# stm32F7_144.net
KiCad netlist of a schematic drawn in Altium Designer
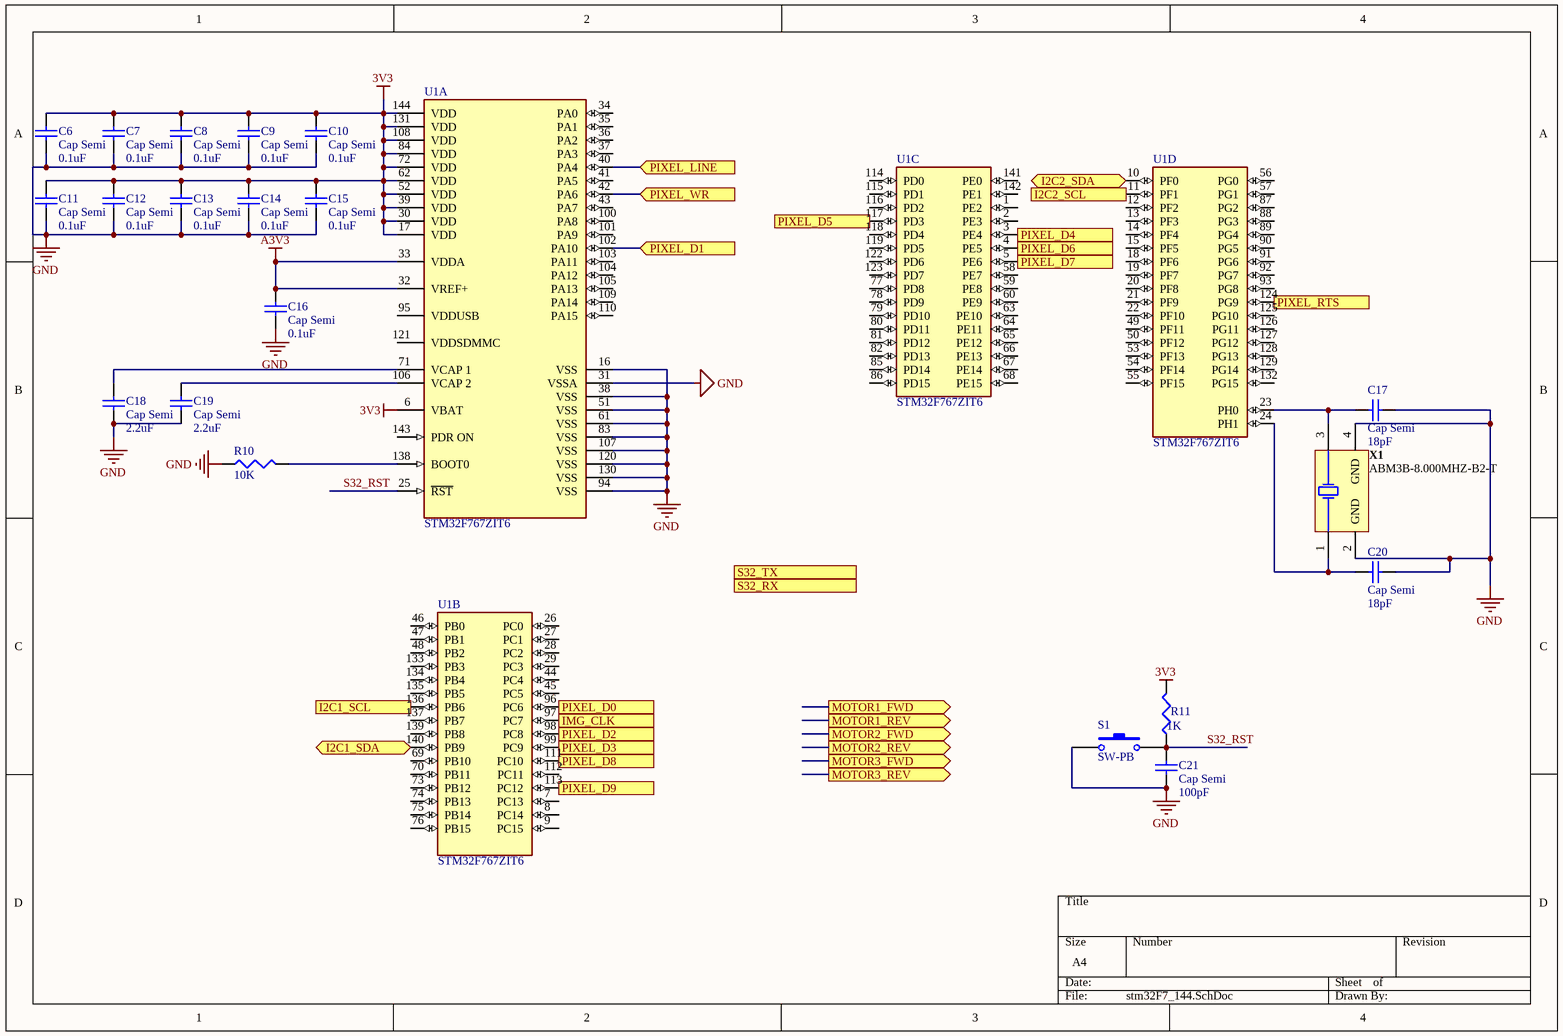
[diagram p0: stm32F7_144.SchDoc]

(export (version "E")
  (design (tool "Eeschema 10.0.6"))
  (components
    (comp (ref "C6")
      (value "Cap Semi")
      (footprint "C1206")
      (description "Capacitor (Semiconductor SIM Model)")
      (fields (field (name "ALTIUM_VALUE") "0.1uF") (field (name "PUBLISHER") "Altium Limited"))
      (libsource (lib "Miscellaneous Devices") (part "Cap Semi"))
    )
    (comp (ref "C7")
      (value "Cap Semi")
      (footprint "C1206")
      (description "Capacitor (Semiconductor SIM Model)")
      (fields (field (name "ALTIUM_VALUE") "0.1uF") (field (name "PUBLISHER") "Altium Limited"))
      (libsource (lib "Miscellaneous Devices") (part "Cap Semi"))
    )
    (comp (ref "C8")
      (value "Cap Semi")
      (footprint "C1206")
      (description "Capacitor (Semiconductor SIM Model)")
      (fields (field (name "ALTIUM_VALUE") "0.1uF") (field (name "PUBLISHER") "Altium Limited"))
      (libsource (lib "Miscellaneous Devices") (part "Cap Semi"))
    )
    (comp (ref "C9")
      (value "Cap Semi")
      (footprint "C1206")
      (description "Capacitor (Semiconductor SIM Model)")
      (fields (field (name "ALTIUM_VALUE") "0.1uF") (field (name "PUBLISHER") "Altium Limited"))
      (libsource (lib "Miscellaneous Devices") (part "Cap Semi"))
    )
    (comp (ref "C10")
      (value "Cap Semi")
      (footprint "C1206")
      (description "Capacitor (Semiconductor SIM Model)")
      (fields (field (name "ALTIUM_VALUE") "0.1uF") (field (name "PUBLISHER") "Altium Limited"))
      (libsource (lib "Miscellaneous Devices") (part "Cap Semi"))
    )
    (comp (ref "C11")
      (value "Cap Semi")
      (footprint "C1206")
      (description "Capacitor (Semiconductor SIM Model)")
      (fields (field (name "ALTIUM_VALUE") "0.1uF") (field (name "PUBLISHER") "Altium Limited"))
      (libsource (lib "Miscellaneous Devices") (part "Cap Semi"))
    )
    (comp (ref "C12")
      (value "Cap Semi")
      (footprint "C1206")
      (description "Capacitor (Semiconductor SIM Model)")
      (fields (field (name "ALTIUM_VALUE") "0.1uF") (field (name "PUBLISHER") "Altium Limited"))
      (libsource (lib "Miscellaneous Devices") (part "Cap Semi"))
    )
    (comp (ref "C13")
      (value "Cap Semi")
      (footprint "C1206")
      (description "Capacitor (Semiconductor SIM Model)")
      (fields (field (name "ALTIUM_VALUE") "0.1uF") (field (name "PUBLISHER") "Altium Limited"))
      (libsource (lib "Miscellaneous Devices") (part "Cap Semi"))
    )
    (comp (ref "C14")
      (value "Cap Semi")
      (footprint "C1206")
      (description "Capacitor (Semiconductor SIM Model)")
      (fields (field (name "ALTIUM_VALUE") "0.1uF") (field (name "PUBLISHER") "Altium Limited"))
      (libsource (lib "Miscellaneous Devices") (part "Cap Semi"))
    )
    (comp (ref "C15")
      (value "Cap Semi")
      (footprint "C1206")
      (description "Capacitor (Semiconductor SIM Model)")
      (fields (field (name "ALTIUM_VALUE") "0.1uF") (field (name "PUBLISHER") "Altium Limited"))
      (libsource (lib "Miscellaneous Devices") (part "Cap Semi"))
    )
    (comp (ref "C16")
      (value "Cap Semi")
      (footprint "C1206")
      (description "Capacitor (Semiconductor SIM Model)")
      (fields (field (name "ALTIUM_VALUE") "0.1uF") (field (name "PUBLISHER") "Altium Limited"))
      (libsource (lib "Miscellaneous Devices") (part "Cap Semi"))
    )
    (comp (ref "C17")
      (value "Cap Semi")
      (footprint "C1206")
      (description "Capacitor (Semiconductor SIM Model)")
      (fields (field (name "ALTIUM_VALUE") "18pF") (field (name "PUBLISHER") "Altium Limited"))
      (libsource (lib "Miscellaneous Devices") (part "Cap Semi"))
    )
    (comp (ref "C18")
      (value "Cap Semi")
      (footprint "C1206")
      (description "Capacitor (Semiconductor SIM Model)")
      (fields (field (name "ALTIUM_VALUE") "2.2uF") (field (name "PUBLISHER") "Altium Limited"))
      (libsource (lib "Miscellaneous Devices") (part "Cap Semi"))
    )
    (comp (ref "C19")
      (value "Cap Semi")
      (footprint "C1206")
      (description "Capacitor (Semiconductor SIM Model)")
      (fields (field (name "ALTIUM_VALUE") "2.2uF") (field (name "PUBLISHER") "Altium Limited"))
      (libsource (lib "Miscellaneous Devices") (part "Cap Semi"))
    )
    (comp (ref "C20")
      (value "Cap Semi")
      (footprint "C1206")
      (description "Capacitor (Semiconductor SIM Model)")
      (fields (field (name "ALTIUM_VALUE") "18pF") (field (name "PUBLISHER") "Altium Limited"))
      (libsource (lib "Miscellaneous Devices") (part "Cap Semi"))
    )
    (comp (ref "C21")
      (value "Cap Semi")
      (footprint "C1206")
      (description "Capacitor (Semiconductor SIM Model)")
      (fields (field (name "ALTIUM_VALUE") "100pF") (field (name "PUBLISHER") "Altium Limited"))
      (libsource (lib "Miscellaneous Devices") (part "Cap Semi"))
    )
    (comp (ref "R10")
      (value "10K")
      (footprint "J1-0603")
      (description "Resistor")
      (fields (field (name "Comment") "Res3") (field (name "PUBLISHER") "Altium Limited"))
      (libsource (lib "Miscellaneous Devices") (part "Res3"))
    )
    (comp (ref "R11")
      (value "1K")
      (footprint "J1-0603")
      (description "Resistor")
      (fields (field (name "Comment") "Res3") (field (name "PUBLISHER") "Altium Limited"))
      (libsource (lib "Miscellaneous Devices") (part "Res3"))
    )
    (comp (ref "S1")
      (value "SW-PB")
      (footprint "SPST-2")
      (description "Switch")
      (fields (field (name "PUBLISHER") "Altium Limited"))
      (libsource (lib "Miscellaneous Devices") (part "SW-PB"))
    )
    (comp (ref "U1")
      (value "STM32F767ZIT6")
      (footprint "FP-LQFP144-1A-MFG")
      (description "IC MCU 32BIT 2MB FLASH 144LQFP")
      (fields
        (field (name "OCTOPART") "https://octopart.com/stm32f767zit6-stmicroelectronics-70527068")
        (field (name "MANUFACTURER") "STMicroelectronics")
      )
      (libsource (lib "Altium Content Vault") (part "5045e889cff10565096e715f5715cbd"))
    )
    (comp (ref "X1")
      (value "ABM3B-8.000MHZ-B2-T")
      (footprint "ABRA-ABM3B_V")
      (description "Ceramic SMD Crystal, 8 MHz, +/- 20 ppm, 200 Ohm, -20 to 70 degC, 4-Pin SMD, RoHS, Tape and Reel")
      (libsource (lib "Altium Content Vault") (part "XTAL-1-3-4"))
    )
  )
  (nets
    (net (code "1") (name "/I2C1_SCL") (class "Default")
      (node (ref "U1") (pin "136") (pinfunction "PB6_136") (pintype "bidirectional"))
    )
    (net (code "2") (name "/I2C1_SDA") (class "Default")
      (node (ref "U1") (pin "140") (pinfunction "PB9_140") (pintype "bidirectional"))
    )
    (net (code "3") (name "/I2C2_SCL") (class "Default")
      (node (ref "U1") (pin "11") (pinfunction "PF1_11") (pintype "bidirectional"))
    )
    (net (code "4") (name "/I2C2_SDA") (class "Default")
      (node (ref "U1") (pin "10") (pinfunction "PF0_10") (pintype "bidirectional"))
    )
    (net (code "5") (name "/IMG_CLK") (class "Default")
      (node (ref "U1") (pin "97") (pinfunction "PC7_97") (pintype "bidirectional"))
    )
    (net (code "12") (name "/PIXEL_D0") (class "Default")
      (node (ref "U1") (pin "96") (pinfunction "PC6_96") (pintype "bidirectional"))
    )
    (net (code "13") (name "/PIXEL_D1") (class "Default")
      (node (ref "U1") (pin "102") (pinfunction "PA10_102") (pintype "bidirectional"))
    )
    (net (code "14") (name "/PIXEL_D2") (class "Default")
      (node (ref "U1") (pin "98") (pinfunction "PC8_98") (pintype "bidirectional"))
    )
    (net (code "15") (name "/PIXEL_D3") (class "Default")
      (node (ref "U1") (pin "99") (pinfunction "PC9_99") (pintype "bidirectional"))
    )
    (net (code "16") (name "/PIXEL_D4") (class "Default")
      (node (ref "U1") (pin "3") (pinfunction "PE4_3") (pintype "bidirectional"))
    )
    (net (code "17") (name "/PIXEL_D5") (class "Default")
      (node (ref "U1") (pin "117") (pinfunction "PD3_117") (pintype "bidirectional"))
    )
    (net (code "18") (name "/PIXEL_D6") (class "Default")
      (node (ref "U1") (pin "4") (pinfunction "PE5_4") (pintype "bidirectional"))
    )
    (net (code "19") (name "/PIXEL_D7") (class "Default")
      (node (ref "U1") (pin "5") (pinfunction "PE6_5") (pintype "bidirectional"))
    )
    (net (code "20") (name "/PIXEL_D8") (class "Default")
      (node (ref "U1") (pin "111") (pinfunction "PC10_111") (pintype "bidirectional"))
    )
    (net (code "21") (name "/PIXEL_D9") (class "Default")
      (node (ref "U1") (pin "113") (pinfunction "PC12_113") (pintype "bidirectional"))
    )
    (net (code "22") (name "/PIXEL_LINE") (class "Default")
      (node (ref "U1") (pin "40") (pinfunction "PA4_40") (pintype "bidirectional"))
    )
    (net (code "23") (name "/PIXEL_RTS") (class "Default")
      (node (ref "U1") (pin "124") (pinfunction "PG9_124") (pintype "bidirectional"))
    )
    (net (code "24") (name "/PIXEL_WR") (class "Default")
      (node (ref "U1") (pin "42") (pinfunction "PA6_42") (pintype "bidirectional"))
    )
    (net (code "25") (name "/S32_RST") (class "Default")
      (node (ref "C21") (pin "2") (pinfunction "2_2") (pintype "passive"))
      (node (ref "R11") (pin "1") (pinfunction "1_1") (pintype "passive"))
      (node (ref "S1") (pin "2") (pinfunction "2_2") (pintype "passive"))
      (node (ref "U1") (pin "25") (pinfunction "~{RST}_25") (pintype "input"))
    )
    (net (code "28") (name "3V3") (class "Default")
      (node (ref "C10") (pin "2") (pinfunction "2_2") (pintype "passive"))
      (node (ref "C11") (pin "2") (pinfunction "2_2") (pintype "passive"))
      (node (ref "C12") (pin "2") (pinfunction "2_2") (pintype "passive"))
      (node (ref "C13") (pin "2") (pinfunction "2_2") (pintype "passive"))
      (node (ref "C14") (pin "2") (pinfunction "2_2") (pintype "passive"))
      (node (ref "C15") (pin "2") (pinfunction "2_2") (pintype "passive"))
      (node (ref "C6") (pin "2") (pinfunction "2_2") (pintype "passive"))
      (node (ref "C7") (pin "2") (pinfunction "2_2") (pintype "passive"))
      (node (ref "C8") (pin "2") (pinfunction "2_2") (pintype "passive"))
      (node (ref "C9") (pin "2") (pinfunction "2_2") (pintype "passive"))
      (node (ref "U1") (pin "108") (pinfunction "VDD_108") (pintype "power_in"))
      (node (ref "U1") (pin "131") (pinfunction "VDD_131") (pintype "power_in"))
      (node (ref "U1") (pin "144") (pinfunction "VDD_144") (pintype "power_in"))
      (node (ref "U1") (pin "17") (pinfunction "VDD_17") (pintype "power_in"))
      (node (ref "U1") (pin "30") (pinfunction "VDD_30") (pintype "power_in"))
      (node (ref "U1") (pin "39") (pinfunction "VDD_39") (pintype "power_in"))
      (node (ref "U1") (pin "52") (pinfunction "VDD_52") (pintype "power_in"))
      (node (ref "U1") (pin "6") (pinfunction "VBAT_6") (pintype "power_in"))
      (node (ref "U1") (pin "62") (pinfunction "VDD_62") (pintype "power_in"))
      (node (ref "U1") (pin "72") (pinfunction "VDD_72") (pintype "power_in"))
      (node (ref "U1") (pin "84") (pinfunction "VDD_84") (pintype "power_in"))
    )
    (net (code "29") (name "A3V3") (class "Default")
      (node (ref "C16") (pin "2") (pinfunction "2_2") (pintype "passive"))
      (node (ref "U1") (pin "32") (pinfunction "VREF+_32") (pintype "power_in"))
      (node (ref "U1") (pin "33") (pinfunction "VDDA_33") (pintype "power_in"))
    )
    (net (code "30") (name "GND") (class "Default")
      (node (ref "C10") (pin "1") (pinfunction "1_1") (pintype "passive"))
      (node (ref "C11") (pin "1") (pinfunction "1_1") (pintype "passive"))
      (node (ref "C12") (pin "1") (pinfunction "1_1") (pintype "passive"))
      (node (ref "C13") (pin "1") (pinfunction "1_1") (pintype "passive"))
      (node (ref "C14") (pin "1") (pinfunction "1_1") (pintype "passive"))
      (node (ref "C15") (pin "1") (pinfunction "1_1") (pintype "passive"))
      (node (ref "C16") (pin "1") (pinfunction "1_1") (pintype "passive"))
      (node (ref "C17") (pin "2") (pinfunction "2_2") (pintype "passive"))
      (node (ref "C18") (pin "1") (pinfunction "1_1") (pintype "passive"))
      (node (ref "C19") (pin "1") (pinfunction "1_1") (pintype "passive"))
      (node (ref "C20") (pin "2") (pinfunction "2_2") (pintype "passive"))
      (node (ref "C21") (pin "1") (pinfunction "1_1") (pintype "passive"))
      (node (ref "C6") (pin "1") (pinfunction "1_1") (pintype "passive"))
      (node (ref "C7") (pin "1") (pinfunction "1_1") (pintype "passive"))
      (node (ref "C8") (pin "1") (pinfunction "1_1") (pintype "passive"))
      (node (ref "C9") (pin "1") (pinfunction "1_1") (pintype "passive"))
      (node (ref "R10") (pin "1") (pinfunction "1_1") (pintype "passive"))
      (node (ref "S1") (pin "1") (pinfunction "1_1") (pintype "passive"))
      (node (ref "U1") (pin "107") (pinfunction "VSS_107") (pintype "power_in"))
      (node (ref "U1") (pin "120") (pinfunction "VSS_120") (pintype "power_in"))
      (node (ref "U1") (pin "130") (pinfunction "VSS_130") (pintype "power_in"))
      (node (ref "U1") (pin "16") (pinfunction "VSS_16") (pintype "power_in"))
      (node (ref "U1") (pin "31") (pinfunction "VSSA_31") (pintype "power_in"))
      (node (ref "U1") (pin "38") (pinfunction "VSS_38") (pintype "power_in"))
      (node (ref "U1") (pin "51") (pinfunction "VSS_51") (pintype "power_in"))
      (node (ref "U1") (pin "61") (pinfunction "VSS_61") (pintype "power_in"))
      (node (ref "U1") (pin "83") (pinfunction "VSS_83") (pintype "power_in"))
      (node (ref "U1") (pin "94") (pinfunction "VSS_94") (pintype "power_in"))
      (node (ref "X1") (pin "2") (pinfunction "GND_2") (pintype "power_in"))
      (node (ref "X1") (pin "4") (pinfunction "GND_4") (pintype "power_in"))
    )
    (net (code "31") (name "Net-(U1A-BOOT0)") (class "Default")
      (node (ref "R10") (pin "2") (pinfunction "2_2") (pintype "passive"))
      (node (ref "U1") (pin "138") (pinfunction "BOOT0_138") (pintype "input"))
    )
    (net (code "32") (name "Net-(U1A-VCAP_1)") (class "Default")
      (node (ref "C18") (pin "2") (pinfunction "2_2") (pintype "passive"))
      (node (ref "U1") (pin "71") (pinfunction "VCAP_1_71") (pintype "power_in"))
    )
    (net (code "33") (name "Net-(U1A-VCAP_2)") (class "Default")
      (node (ref "C19") (pin "2") (pinfunction "2_2") (pintype "passive"))
      (node (ref "U1") (pin "106") (pinfunction "VCAP_2_106") (pintype "power_in"))
    )
    (net (code "34") (name "Net-(U1D-PH0)") (class "Default")
      (node (ref "C17") (pin "1") (pinfunction "1_1") (pintype "passive"))
      (node (ref "U1") (pin "23") (pinfunction "PH0_23") (pintype "bidirectional"))
      (node (ref "X1") (pin "3") (pinfunction "X2_3") (pintype "passive"))
    )
    (net (code "35") (name "Net-(U1D-PH1)") (class "Default")
      (node (ref "C20") (pin "1") (pinfunction "1_1") (pintype "passive"))
      (node (ref "U1") (pin "24") (pinfunction "PH1_24") (pintype "bidirectional"))
      (node (ref "X1") (pin "1") (pinfunction "X1_1") (pintype "passive"))
    )
    (net (code "36") (name "unconnected-(R11-Pad2)") (class "Default")
      (node (ref "R11") (pin "2") (pinfunction "2_2") (pintype "passive"))
    )
    (net (code "37") (name "unconnected-(U1A-PA0-Pad34)") (class "Default")
      (node (ref "U1") (pin "34") (pinfunction "PA0_34") (pintype "bidirectional"))
    )
    (net (code "38") (name "unconnected-(U1A-PA1-Pad35)") (class "Default")
      (node (ref "U1") (pin "35") (pinfunction "PA1_35") (pintype "bidirectional"))
    )
    (net (code "39") (name "unconnected-(U1A-PA2-Pad36)") (class "Default")
      (node (ref "U1") (pin "36") (pinfunction "PA2_36") (pintype "bidirectional"))
    )
    (net (code "40") (name "unconnected-(U1A-PA3-Pad37)") (class "Default")
      (node (ref "U1") (pin "37") (pinfunction "PA3_37") (pintype "bidirectional"))
    )
    (net (code "41") (name "unconnected-(U1A-PA5-Pad41)") (class "Default")
      (node (ref "U1") (pin "41") (pinfunction "PA5_41") (pintype "bidirectional"))
    )
    (net (code "42") (name "unconnected-(U1A-PA7-Pad43)") (class "Default")
      (node (ref "U1") (pin "43") (pinfunction "PA7_43") (pintype "bidirectional"))
    )
    (net (code "43") (name "unconnected-(U1A-PA8-Pad100)") (class "Default")
      (node (ref "U1") (pin "100") (pinfunction "PA8_100") (pintype "bidirectional"))
    )
    (net (code "44") (name "unconnected-(U1A-PA9-Pad101)") (class "Default")
      (node (ref "U1") (pin "101") (pinfunction "PA9_101") (pintype "bidirectional"))
    )
    (net (code "45") (name "unconnected-(U1A-PA11-Pad103)") (class "Default")
      (node (ref "U1") (pin "103") (pinfunction "PA11_103") (pintype "bidirectional"))
    )
    (net (code "46") (name "unconnected-(U1A-PA12-Pad104)") (class "Default")
      (node (ref "U1") (pin "104") (pinfunction "PA12_104") (pintype "bidirectional"))
    )
    (net (code "47") (name "unconnected-(U1A-PA13-Pad105)") (class "Default")
      (node (ref "U1") (pin "105") (pinfunction "PA13_105") (pintype "bidirectional"))
    )
    (net (code "48") (name "unconnected-(U1A-PA14-Pad109)") (class "Default")
      (node (ref "U1") (pin "109") (pinfunction "PA14_109") (pintype "bidirectional"))
    )
    (net (code "49") (name "unconnected-(U1A-PA15-Pad110)") (class "Default")
      (node (ref "U1") (pin "110") (pinfunction "PA15_110") (pintype "bidirectional"))
    )
    (net (code "50") (name "unconnected-(U1A-PDR_ON-Pad143)") (class "Default")
      (node (ref "U1") (pin "143") (pinfunction "PDR_ON_143") (pintype "input"))
    )
    (net (code "51") (name "unconnected-(U1A-VDDSDMMC-Pad121)") (class "Default")
      (node (ref "U1") (pin "121") (pinfunction "VDDSDMMC_121") (pintype "power_in"))
    )
    (net (code "52") (name "unconnected-(U1A-VDDUSB-Pad95)") (class "Default")
      (node (ref "U1") (pin "95") (pinfunction "VDDUSB_95") (pintype "power_in"))
    )
    (net (code "53") (name "unconnected-(U1B-PB0-Pad46)") (class "Default")
      (node (ref "U1") (pin "46") (pinfunction "PB0_46") (pintype "bidirectional"))
    )
    (net (code "54") (name "unconnected-(U1B-PB1-Pad47)") (class "Default")
      (node (ref "U1") (pin "47") (pinfunction "PB1_47") (pintype "bidirectional"))
    )
    (net (code "55") (name "unconnected-(U1B-PB2-Pad48)") (class "Default")
      (node (ref "U1") (pin "48") (pinfunction "PB2_48") (pintype "bidirectional"))
    )
    (net (code "56") (name "unconnected-(U1B-PB3-Pad133)") (class "Default")
      (node (ref "U1") (pin "133") (pinfunction "PB3_133") (pintype "bidirectional"))
    )
    (net (code "57") (name "unconnected-(U1B-PB4-Pad134)") (class "Default")
      (node (ref "U1") (pin "134") (pinfunction "PB4_134") (pintype "bidirectional"))
    )
    (net (code "58") (name "unconnected-(U1B-PB5-Pad135)") (class "Default")
      (node (ref "U1") (pin "135") (pinfunction "PB5_135") (pintype "bidirectional"))
    )
    (net (code "59") (name "unconnected-(U1B-PB7-Pad137)") (class "Default")
      (node (ref "U1") (pin "137") (pinfunction "PB7_137") (pintype "bidirectional"))
    )
    (net (code "60") (name "unconnected-(U1B-PB8-Pad139)") (class "Default")
      (node (ref "U1") (pin "139") (pinfunction "PB8_139") (pintype "bidirectional"))
    )
    (net (code "61") (name "unconnected-(U1B-PB10-Pad69)") (class "Default")
      (node (ref "U1") (pin "69") (pinfunction "PB10_69") (pintype "bidirectional"))
    )
    (net (code "62") (name "unconnected-(U1B-PB11-Pad70)") (class "Default")
      (node (ref "U1") (pin "70") (pinfunction "PB11_70") (pintype "bidirectional"))
    )
    (net (code "63") (name "unconnected-(U1B-PB12-Pad73)") (class "Default")
      (node (ref "U1") (pin "73") (pinfunction "PB12_73") (pintype "bidirectional"))
    )
    (net (code "64") (name "unconnected-(U1B-PB13-Pad74)") (class "Default")
      (node (ref "U1") (pin "74") (pinfunction "PB13_74") (pintype "bidirectional"))
    )
    (net (code "65") (name "unconnected-(U1B-PB14-Pad75)") (class "Default")
      (node (ref "U1") (pin "75") (pinfunction "PB14_75") (pintype "bidirectional"))
    )
    (net (code "66") (name "unconnected-(U1B-PB15-Pad76)") (class "Default")
      (node (ref "U1") (pin "76") (pinfunction "PB15_76") (pintype "bidirectional"))
    )
    (net (code "67") (name "unconnected-(U1B-PC0-Pad26)") (class "Default")
      (node (ref "U1") (pin "26") (pinfunction "PC0_26") (pintype "bidirectional"))
    )
    (net (code "68") (name "unconnected-(U1B-PC1-Pad27)") (class "Default")
      (node (ref "U1") (pin "27") (pinfunction "PC1_27") (pintype "bidirectional"))
    )
    (net (code "69") (name "unconnected-(U1B-PC2-Pad28)") (class "Default")
      (node (ref "U1") (pin "28") (pinfunction "PC2_28") (pintype "bidirectional"))
    )
    (net (code "70") (name "unconnected-(U1B-PC3-Pad29)") (class "Default")
      (node (ref "U1") (pin "29") (pinfunction "PC3_29") (pintype "bidirectional"))
    )
    (net (code "71") (name "unconnected-(U1B-PC4-Pad44)") (class "Default")
      (node (ref "U1") (pin "44") (pinfunction "PC4_44") (pintype "bidirectional"))
    )
    (net (code "72") (name "unconnected-(U1B-PC5-Pad45)") (class "Default")
      (node (ref "U1") (pin "45") (pinfunction "PC5_45") (pintype "bidirectional"))
    )
    (net (code "73") (name "unconnected-(U1B-PC11-Pad112)") (class "Default")
      (node (ref "U1") (pin "112") (pinfunction "PC11_112") (pintype "bidirectional"))
    )
    (net (code "74") (name "unconnected-(U1B-PC13-Pad7)") (class "Default")
      (node (ref "U1") (pin "7") (pinfunction "PC13_7") (pintype "bidirectional"))
    )
    (net (code "75") (name "unconnected-(U1B-PC14-Pad8)") (class "Default")
      (node (ref "U1") (pin "8") (pinfunction "PC14_8") (pintype "bidirectional"))
    )
    (net (code "76") (name "unconnected-(U1B-PC15-Pad9)") (class "Default")
      (node (ref "U1") (pin "9") (pinfunction "PC15_9") (pintype "bidirectional"))
    )
    (net (code "77") (name "unconnected-(U1C-PD0-Pad114)") (class "Default")
      (node (ref "U1") (pin "114") (pinfunction "PD0_114") (pintype "bidirectional"))
    )
    (net (code "78") (name "unconnected-(U1C-PD1-Pad115)") (class "Default")
      (node (ref "U1") (pin "115") (pinfunction "PD1_115") (pintype "bidirectional"))
    )
    (net (code "79") (name "unconnected-(U1C-PD2-Pad116)") (class "Default")
      (node (ref "U1") (pin "116") (pinfunction "PD2_116") (pintype "bidirectional"))
    )
    (net (code "80") (name "unconnected-(U1C-PD4-Pad118)") (class "Default")
      (node (ref "U1") (pin "118") (pinfunction "PD4_118") (pintype "bidirectional"))
    )
    (net (code "81") (name "unconnected-(U1C-PD5-Pad119)") (class "Default")
      (node (ref "U1") (pin "119") (pinfunction "PD5_119") (pintype "bidirectional"))
    )
    (net (code "82") (name "unconnected-(U1C-PD6-Pad122)") (class "Default")
      (node (ref "U1") (pin "122") (pinfunction "PD6_122") (pintype "bidirectional"))
    )
    (net (code "83") (name "unconnected-(U1C-PD7-Pad123)") (class "Default")
      (node (ref "U1") (pin "123") (pinfunction "PD7_123") (pintype "bidirectional"))
    )
    (net (code "84") (name "unconnected-(U1C-PD8-Pad77)") (class "Default")
      (node (ref "U1") (pin "77") (pinfunction "PD8_77") (pintype "bidirectional"))
    )
    (net (code "85") (name "unconnected-(U1C-PD9-Pad78)") (class "Default")
      (node (ref "U1") (pin "78") (pinfunction "PD9_78") (pintype "bidirectional"))
    )
    (net (code "86") (name "unconnected-(U1C-PD10-Pad79)") (class "Default")
      (node (ref "U1") (pin "79") (pinfunction "PD10_79") (pintype "bidirectional"))
    )
    (net (code "87") (name "unconnected-(U1C-PD11-Pad80)") (class "Default")
      (node (ref "U1") (pin "80") (pinfunction "PD11_80") (pintype "bidirectional"))
    )
    (net (code "88") (name "unconnected-(U1C-PD12-Pad81)") (class "Default")
      (node (ref "U1") (pin "81") (pinfunction "PD12_81") (pintype "bidirectional"))
    )
    (net (code "89") (name "unconnected-(U1C-PD13-Pad82)") (class "Default")
      (node (ref "U1") (pin "82") (pinfunction "PD13_82") (pintype "bidirectional"))
    )
    (net (code "90") (name "unconnected-(U1C-PD14-Pad85)") (class "Default")
      (node (ref "U1") (pin "85") (pinfunction "PD14_85") (pintype "bidirectional"))
    )
    (net (code "91") (name "unconnected-(U1C-PD15-Pad86)") (class "Default")
      (node (ref "U1") (pin "86") (pinfunction "PD15_86") (pintype "bidirectional"))
    )
    (net (code "92") (name "unconnected-(U1C-PE0-Pad141)") (class "Default")
      (node (ref "U1") (pin "141") (pinfunction "PE0_141") (pintype "bidirectional"))
    )
    (net (code "93") (name "unconnected-(U1C-PE1-Pad142)") (class "Default")
      (node (ref "U1") (pin "142") (pinfunction "PE1_142") (pintype "bidirectional"))
    )
    (net (code "94") (name "unconnected-(U1C-PE2-Pad1)") (class "Default")
      (node (ref "U1") (pin "1") (pinfunction "PE2_1") (pintype "bidirectional"))
    )
    (net (code "95") (name "unconnected-(U1C-PE3-Pad2)") (class "Default")
      (node (ref "U1") (pin "2") (pinfunction "PE3_2") (pintype "bidirectional"))
    )
    (net (code "96") (name "unconnected-(U1C-PE7-Pad58)") (class "Default")
      (node (ref "U1") (pin "58") (pinfunction "PE7_58") (pintype "bidirectional"))
    )
    (net (code "97") (name "unconnected-(U1C-PE8-Pad59)") (class "Default")
      (node (ref "U1") (pin "59") (pinfunction "PE8_59") (pintype "bidirectional"))
    )
    (net (code "98") (name "unconnected-(U1C-PE9-Pad60)") (class "Default")
      (node (ref "U1") (pin "60") (pinfunction "PE9_60") (pintype "bidirectional"))
    )
    (net (code "99") (name "unconnected-(U1C-PE10-Pad63)") (class "Default")
      (node (ref "U1") (pin "63") (pinfunction "PE10_63") (pintype "bidirectional"))
    )
    (net (code "100") (name "unconnected-(U1C-PE11-Pad64)") (class "Default")
      (node (ref "U1") (pin "64") (pinfunction "PE11_64") (pintype "bidirectional"))
    )
    (net (code "101") (name "unconnected-(U1C-PE12-Pad65)") (class "Default")
      (node (ref "U1") (pin "65") (pinfunction "PE12_65") (pintype "bidirectional"))
    )
    (net (code "102") (name "unconnected-(U1C-PE13-Pad66)") (class "Default")
      (node (ref "U1") (pin "66") (pinfunction "PE13_66") (pintype "bidirectional"))
    )
    (net (code "103") (name "unconnected-(U1C-PE14-Pad67)") (class "Default")
      (node (ref "U1") (pin "67") (pinfunction "PE14_67") (pintype "bidirectional"))
    )
    (net (code "104") (name "unconnected-(U1C-PE15-Pad68)") (class "Default")
      (node (ref "U1") (pin "68") (pinfunction "PE15_68") (pintype "bidirectional"))
    )
    (net (code "105") (name "unconnected-(U1D-PF2-Pad12)") (class "Default")
      (node (ref "U1") (pin "12") (pinfunction "PF2_12") (pintype "bidirectional"))
    )
    (net (code "106") (name "unconnected-(U1D-PF3-Pad13)") (class "Default")
      (node (ref "U1") (pin "13") (pinfunction "PF3_13") (pintype "bidirectional"))
    )
    (net (code "107") (name "unconnected-(U1D-PF4-Pad14)") (class "Default")
      (node (ref "U1") (pin "14") (pinfunction "PF4_14") (pintype "bidirectional"))
    )
    (net (code "108") (name "unconnected-(U1D-PF5-Pad15)") (class "Default")
      (node (ref "U1") (pin "15") (pinfunction "PF5_15") (pintype "bidirectional"))
    )
    (net (code "109") (name "unconnected-(U1D-PF6-Pad18)") (class "Default")
      (node (ref "U1") (pin "18") (pinfunction "PF6_18") (pintype "bidirectional"))
    )
    (net (code "110") (name "unconnected-(U1D-PF7-Pad19)") (class "Default")
      (node (ref "U1") (pin "19") (pinfunction "PF7_19") (pintype "bidirectional"))
    )
    (net (code "111") (name "unconnected-(U1D-PF8-Pad20)") (class "Default")
      (node (ref "U1") (pin "20") (pinfunction "PF8_20") (pintype "bidirectional"))
    )
    (net (code "112") (name "unconnected-(U1D-PF9-Pad21)") (class "Default")
      (node (ref "U1") (pin "21") (pinfunction "PF9_21") (pintype "bidirectional"))
    )
    (net (code "113") (name "unconnected-(U1D-PF10-Pad22)") (class "Default")
      (node (ref "U1") (pin "22") (pinfunction "PF10_22") (pintype "bidirectional"))
    )
    (net (code "114") (name "unconnected-(U1D-PF11-Pad49)") (class "Default")
      (node (ref "U1") (pin "49") (pinfunction "PF11_49") (pintype "bidirectional"))
    )
    (net (code "115") (name "unconnected-(U1D-PF12-Pad50)") (class "Default")
      (node (ref "U1") (pin "50") (pinfunction "PF12_50") (pintype "bidirectional"))
    )
    (net (code "116") (name "unconnected-(U1D-PF13-Pad53)") (class "Default")
      (node (ref "U1") (pin "53") (pinfunction "PF13_53") (pintype "bidirectional"))
    )
    (net (code "117") (name "unconnected-(U1D-PF14-Pad54)") (class "Default")
      (node (ref "U1") (pin "54") (pinfunction "PF14_54") (pintype "bidirectional"))
    )
    (net (code "118") (name "unconnected-(U1D-PF15-Pad55)") (class "Default")
      (node (ref "U1") (pin "55") (pinfunction "PF15_55") (pintype "bidirectional"))
    )
    (net (code "119") (name "unconnected-(U1D-PG0-Pad56)") (class "Default")
      (node (ref "U1") (pin "56") (pinfunction "PG0_56") (pintype "bidirectional"))
    )
    (net (code "120") (name "unconnected-(U1D-PG1-Pad57)") (class "Default")
      (node (ref "U1") (pin "57") (pinfunction "PG1_57") (pintype "bidirectional"))
    )
    (net (code "121") (name "unconnected-(U1D-PG2-Pad87)") (class "Default")
      (node (ref "U1") (pin "87") (pinfunction "PG2_87") (pintype "bidirectional"))
    )
    (net (code "122") (name "unconnected-(U1D-PG3-Pad88)") (class "Default")
      (node (ref "U1") (pin "88") (pinfunction "PG3_88") (pintype "bidirectional"))
    )
    (net (code "123") (name "unconnected-(U1D-PG4-Pad89)") (class "Default")
      (node (ref "U1") (pin "89") (pinfunction "PG4_89") (pintype "bidirectional"))
    )
    (net (code "124") (name "unconnected-(U1D-PG5-Pad90)") (class "Default")
      (node (ref "U1") (pin "90") (pinfunction "PG5_90") (pintype "bidirectional"))
    )
    (net (code "125") (name "unconnected-(U1D-PG6-Pad91)") (class "Default")
      (node (ref "U1") (pin "91") (pinfunction "PG6_91") (pintype "bidirectional"))
    )
    (net (code "126") (name "unconnected-(U1D-PG7-Pad92)") (class "Default")
      (node (ref "U1") (pin "92") (pinfunction "PG7_92") (pintype "bidirectional"))
    )
    (net (code "127") (name "unconnected-(U1D-PG8-Pad93)") (class "Default")
      (node (ref "U1") (pin "93") (pinfunction "PG8_93") (pintype "bidirectional"))
    )
    (net (code "128") (name "unconnected-(U1D-PG10-Pad125)") (class "Default")
      (node (ref "U1") (pin "125") (pinfunction "PG10_125") (pintype "bidirectional"))
    )
    (net (code "129") (name "unconnected-(U1D-PG11-Pad126)") (class "Default")
      (node (ref "U1") (pin "126") (pinfunction "PG11_126") (pintype "bidirectional"))
    )
    (net (code "130") (name "unconnected-(U1D-PG12-Pad127)") (class "Default")
      (node (ref "U1") (pin "127") (pinfunction "PG12_127") (pintype "bidirectional"))
    )
    (net (code "131") (name "unconnected-(U1D-PG13-Pad128)") (class "Default")
      (node (ref "U1") (pin "128") (pinfunction "PG13_128") (pintype "bidirectional"))
    )
    (net (code "132") (name "unconnected-(U1D-PG14-Pad129)") (class "Default")
      (node (ref "U1") (pin "129") (pinfunction "PG14_129") (pintype "bidirectional"))
    )
    (net (code "133") (name "unconnected-(U1D-PG15-Pad132)") (class "Default")
      (node (ref "U1") (pin "132") (pinfunction "PG15_132") (pintype "bidirectional"))
    )
  )
)
